# HM_SENSOR_HOLDER.net
KiCad netlist of a schematic drawn in EAGLE
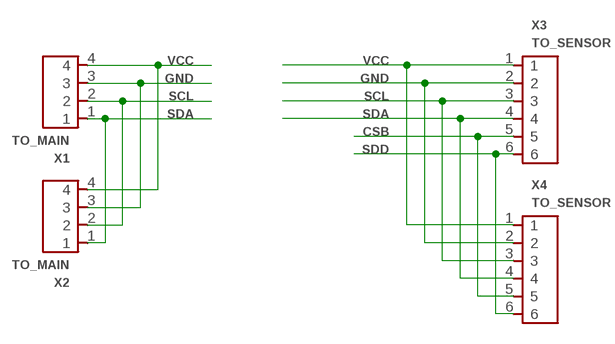
[diagram p0: schematic, sheet 1]

(export (version "E")
  (design (tool "Eeschema 10.0.6"))
  (components
    (comp (ref "X1")
      (value "TO_MAIN")
      (footprint "eagle-import:PIN4X1_2.54MM")
      (libsource (lib "eagle-import") (part "PIN4X1(2.54MM)"))
    )
    (comp (ref "X2")
      (value "TO_MAIN")
      (footprint "eagle-import:PIN4X1_2.54MM_SIDE_BOARD")
      (libsource (lib "eagle-import") (part "PIN4X1(2.54MM_SIDE)"))
    )
    (comp (ref "X3")
      (value "TO_SENSOR")
      (footprint "eagle-import:PIN6X1_2.54MM")
      (libsource (lib "eagle-import") (part "PIN6X1(2.54MM)"))
    )
    (comp (ref "X4")
      (value "TO_SENSOR")
      (footprint "eagle-import:PIN6X1_2.54MM_SIDE_BOARD")
      (libsource (lib "eagle-import") (part "PIN6X1(2.54MM_SIDE)"))
    )
  )
  (nets
    (net (code "1") (name "/CSB") (class "Default")
      (node (ref "X3") (pin "5") (pinfunction "5_5") (pintype "bidirectional"))
      (node (ref "X4") (pin "5") (pinfunction "5_5") (pintype "bidirectional"))
    )
    (net (code "2") (name "/GND") (class "Default")
      (node (ref "X1") (pin "3") (pinfunction "3_3") (pintype "bidirectional"))
      (node (ref "X2") (pin "3") (pinfunction "3_3") (pintype "bidirectional"))
      (node (ref "X3") (pin "2") (pinfunction "2_2") (pintype "bidirectional"))
      (node (ref "X4") (pin "2") (pinfunction "2_2") (pintype "bidirectional"))
    )
    (net (code "3") (name "/SCL") (class "Default")
      (node (ref "X1") (pin "2") (pinfunction "2_2") (pintype "bidirectional"))
      (node (ref "X2") (pin "2") (pinfunction "2_2") (pintype "bidirectional"))
      (node (ref "X3") (pin "3") (pinfunction "3_3") (pintype "bidirectional"))
      (node (ref "X4") (pin "3") (pinfunction "3_3") (pintype "bidirectional"))
    )
    (net (code "4") (name "/SDA") (class "Default")
      (node (ref "X1") (pin "1") (pinfunction "1_1") (pintype "bidirectional"))
      (node (ref "X2") (pin "1") (pinfunction "1_1") (pintype "bidirectional"))
      (node (ref "X3") (pin "4") (pinfunction "4_4") (pintype "bidirectional"))
      (node (ref "X4") (pin "4") (pinfunction "4_4") (pintype "bidirectional"))
    )
    (net (code "5") (name "/SDD") (class "Default")
      (node (ref "X3") (pin "6") (pinfunction "6_6") (pintype "bidirectional"))
      (node (ref "X4") (pin "6") (pinfunction "6_6") (pintype "bidirectional"))
    )
    (net (code "6") (name "/VCC") (class "Default")
      (node (ref "X1") (pin "4") (pinfunction "4_4") (pintype "bidirectional"))
      (node (ref "X2") (pin "4") (pinfunction "4_4") (pintype "bidirectional"))
      (node (ref "X3") (pin "1") (pinfunction "1_1") (pintype "bidirectional"))
      (node (ref "X4") (pin "1") (pinfunction "1_1") (pintype "bidirectional"))
    )
  )
)
